# icboard.net
KiCad netlist of a schematic drawn in EAGLE
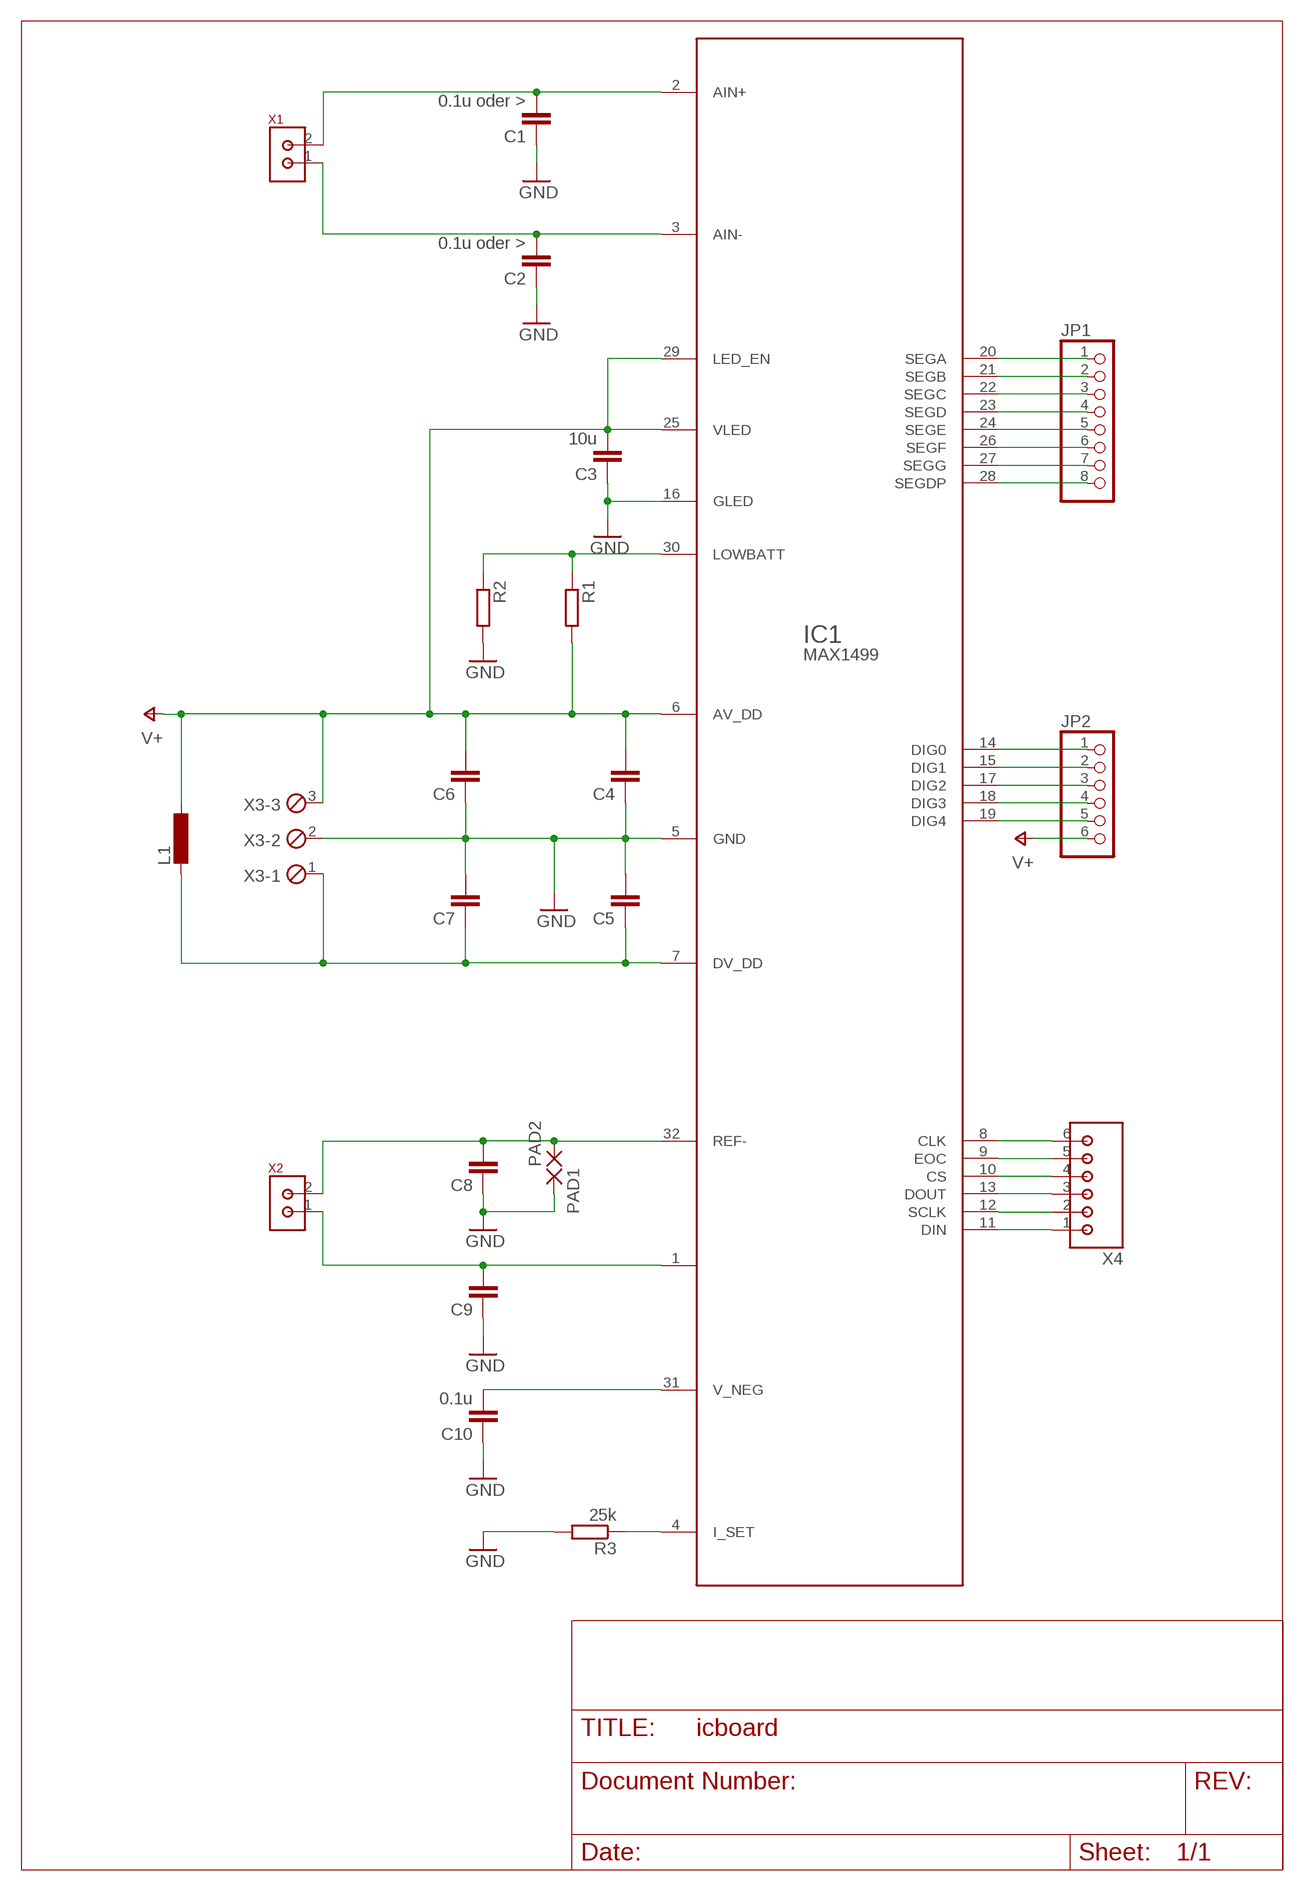
[diagram p0: schematic, sheet 1]

(export (version "E")
  (design (tool "Eeschema 10.0.6"))
  (components
    (comp (ref "C1")
      (value "0.1u oder >")
      (footprint "eagle-import:C0603")
      (libsource (lib "eagle-import") (part "C-EUC0603"))
    )
    (comp (ref "C2")
      (value "0.1u oder >")
      (footprint "eagle-import:C0603")
      (libsource (lib "eagle-import") (part "C-EUC0603"))
    )
    (comp (ref "C3")
      (value "10u")
      (footprint "eagle-import:C0603")
      (libsource (lib "eagle-import") (part "C-EUC0603"))
    )
    (comp (ref "C4")
      (value "C-EUC0603")
      (footprint "eagle-import:C0603")
      (libsource (lib "eagle-import") (part "C-EUC0603"))
    )
    (comp (ref "C5")
      (value "C-EUC0603")
      (footprint "eagle-import:C0603")
      (libsource (lib "eagle-import") (part "C-EUC0603"))
    )
    (comp (ref "C6")
      (value "C-EUC0603")
      (footprint "eagle-import:C0603")
      (libsource (lib "eagle-import") (part "C-EUC0603"))
    )
    (comp (ref "C7")
      (value "C-EUC0603")
      (footprint "eagle-import:C0603")
      (libsource (lib "eagle-import") (part "C-EUC0603"))
    )
    (comp (ref "C8")
      (value "C-EUC0603")
      (footprint "eagle-import:C0603")
      (libsource (lib "eagle-import") (part "C-EUC0603"))
    )
    (comp (ref "C9")
      (value "C-EUC0603")
      (footprint "eagle-import:C0603")
      (libsource (lib "eagle-import") (part "C-EUC0603"))
    )
    (comp (ref "C10")
      (value "0.1u")
      (footprint "eagle-import:C0603")
      (libsource (lib "eagle-import") (part "C-EUC0603"))
    )
    (comp (ref "IC1")
      (value "MAX1499")
      (footprint "eagle-import:TQFP32-08")
      (libsource (lib "eagle-import") (part "MAX1499"))
    )
    (comp (ref "JP1")
      (value "PINHD-1X8")
      (footprint "eagle-import:1X08")
      (libsource (lib "eagle-import") (part "PINHD-1X8"))
    )
    (comp (ref "JP2")
      (value "PINHD-1X6")
      (footprint "eagle-import:1X06")
      (libsource (lib "eagle-import") (part "PINHD-1X6"))
    )
    (comp (ref "L1")
      (value "L-EUL1812")
      (footprint "eagle-import:L1812")
      (libsource (lib "eagle-import") (part "L-EUL1812"))
    )
    (comp (ref "PAD1")
      (value "SMD2")
      (footprint "eagle-import:SMD1,27-2,54")
      (libsource (lib "eagle-import") (part "SMD2"))
    )
    (comp (ref "PAD2")
      (value "SMD2")
      (footprint "eagle-import:SMD1,27-2,54")
      (libsource (lib "eagle-import") (part "SMD2"))
    )
    (comp (ref "R1")
      (value "R-EU_R0603")
      (footprint "eagle-import:R0603")
      (libsource (lib "eagle-import") (part "R-EU_R0603"))
    )
    (comp (ref "R2")
      (value "R-EU_R0603")
      (footprint "eagle-import:R0603")
      (libsource (lib "eagle-import") (part "R-EU_R0603"))
    )
    (comp (ref "R3")
      (value "25k")
      (footprint "eagle-import:R0603")
      (libsource (lib "eagle-import") (part "R-EU_R0603"))
    )
    (comp (ref "X1")
      (value "MOLEX_CON2_2P")
      (footprint "eagle-import:CON2_2P")
      (libsource (lib "eagle-import") (part "MOLEX_CON2_2P"))
    )
    (comp (ref "X2")
      (value "MOLEX_CON2_2P")
      (footprint "eagle-import:CON2_2P")
      (libsource (lib "eagle-import") (part "MOLEX_CON2_2P"))
    )
    (comp (ref "X3")
      (value "MPT3")
      (footprint "eagle-import:3POL254")
      (libsource (lib "eagle-import") (part "MPT3"))
    )
    (comp (ref "X4")
      (value "MOLEX_CON2_6P")
      (footprint "eagle-import:CON2_6P")
      (libsource (lib "eagle-import") (part "MOLEX_CON2_6P"))
    )
  )
  (nets
    (net (code "1") (name "GND") (class "Default")
      (node (ref "C1") (pin "1") (pinfunction "1_1") (pintype "passive"))
      (node (ref "C10") (pin "1") (pinfunction "1_1") (pintype "passive"))
      (node (ref "C2") (pin "1") (pinfunction "1_1") (pintype "passive"))
      (node (ref "C3") (pin "1") (pinfunction "1_1") (pintype "passive"))
      (node (ref "C4") (pin "1") (pinfunction "1_1") (pintype "passive"))
      (node (ref "C5") (pin "2") (pinfunction "2_2") (pintype "passive"))
      (node (ref "C6") (pin "1") (pinfunction "1_1") (pintype "passive"))
      (node (ref "C7") (pin "2") (pinfunction "2_2") (pintype "passive"))
      (node (ref "C8") (pin "1") (pinfunction "1_1") (pintype "passive"))
      (node (ref "C9") (pin "1") (pinfunction "1_1") (pintype "passive"))
      (node (ref "IC1") (pin "16") (pinfunction "GLED_16") (pintype "input"))
      (node (ref "IC1") (pin "5") (pinfunction "GND_5") (pintype "passive"))
      (node (ref "PAD1") (pin "1") (pinfunction "P_1") (pintype "passive"))
      (node (ref "R2") (pin "2") (pinfunction "2_2") (pintype "passive"))
      (node (ref "R3") (pin "2") (pinfunction "2_2") (pintype "passive"))
      (node (ref "X3") (pin "2") (pinfunction "1_2") (pintype "passive"))
    )
    (net (code "2") (name "Net-(IC1-AIN+)") (class "Default")
      (node (ref "C1") (pin "2") (pinfunction "2_2") (pintype "passive"))
      (node (ref "IC1") (pin "2") (pinfunction "AIN+_2") (pintype "input"))
      (node (ref "X1") (pin "2") (pinfunction "P$2_2") (pintype "bidirectional"))
    )
    (net (code "3") (name "Net-(IC1-AIN-)") (class "Default")
      (node (ref "C2") (pin "2") (pinfunction "2_2") (pintype "passive"))
      (node (ref "IC1") (pin "3") (pinfunction "AIN-_3") (pintype "input"))
      (node (ref "X1") (pin "1") (pinfunction "P$1_1") (pintype "bidirectional"))
    )
    (net (code "4") (name "Net-(IC1-CLK)") (class "Default")
      (node (ref "IC1") (pin "8") (pinfunction "CLK_8") (pintype "input"))
      (node (ref "X4") (pin "6") (pinfunction "6_6") (pintype "bidirectional"))
    )
    (net (code "5") (name "Net-(IC1-CS)") (class "Default")
      (node (ref "IC1") (pin "10") (pinfunction "CS_10") (pintype "input"))
      (node (ref "X4") (pin "4") (pinfunction "4_4") (pintype "bidirectional"))
    )
    (net (code "6") (name "Net-(IC1-DIG0)") (class "Default")
      (node (ref "IC1") (pin "14") (pinfunction "DIG0_14") (pintype "input"))
      (node (ref "JP2") (pin "1") (pinfunction "1_1") (pintype "passive"))
    )
    (net (code "7") (name "Net-(IC1-DIG1)") (class "Default")
      (node (ref "IC1") (pin "15") (pinfunction "DIG1_15") (pintype "input"))
      (node (ref "JP2") (pin "2") (pinfunction "2_2") (pintype "passive"))
    )
    (net (code "8") (name "Net-(IC1-DIG2)") (class "Default")
      (node (ref "IC1") (pin "17") (pinfunction "DIG2_17") (pintype "input"))
      (node (ref "JP2") (pin "3") (pinfunction "3_3") (pintype "passive"))
    )
    (net (code "9") (name "Net-(IC1-DIG3)") (class "Default")
      (node (ref "IC1") (pin "18") (pinfunction "DIG3_18") (pintype "input"))
      (node (ref "JP2") (pin "4") (pinfunction "4_4") (pintype "passive"))
    )
    (net (code "10") (name "Net-(IC1-DIG4)") (class "Default")
      (node (ref "IC1") (pin "19") (pinfunction "DIG4_19") (pintype "input"))
      (node (ref "JP2") (pin "5") (pinfunction "5_5") (pintype "passive"))
    )
    (net (code "11") (name "Net-(IC1-DIN)") (class "Default")
      (node (ref "IC1") (pin "11") (pinfunction "DIN_11") (pintype "input"))
      (node (ref "X4") (pin "1") (pinfunction "1_1") (pintype "bidirectional"))
    )
    (net (code "12") (name "Net-(IC1-DOUT)") (class "Default")
      (node (ref "IC1") (pin "13") (pinfunction "DOUT_13") (pintype "output"))
      (node (ref "X4") (pin "3") (pinfunction "3_3") (pintype "bidirectional"))
    )
    (net (code "13") (name "Net-(IC1-DV_DD)") (class "Default")
      (node (ref "C5") (pin "1") (pinfunction "1_1") (pintype "passive"))
      (node (ref "C7") (pin "1") (pinfunction "1_1") (pintype "passive"))
      (node (ref "IC1") (pin "7") (pinfunction "DV_DD_7") (pintype "passive"))
      (node (ref "L1") (pin "2") (pinfunction "2_2") (pintype "passive"))
      (node (ref "X3") (pin "1") (pinfunction "1_1") (pintype "passive"))
    )
    (net (code "14") (name "Net-(IC1-EOC)") (class "Default")
      (node (ref "IC1") (pin "9") (pinfunction "EOC_9") (pintype "output"))
      (node (ref "X4") (pin "5") (pinfunction "5_5") (pintype "bidirectional"))
    )
    (net (code "15") (name "Net-(IC1-I_SET)") (class "Default")
      (node (ref "IC1") (pin "4") (pinfunction "I_SET_4") (pintype "input"))
      (node (ref "R3") (pin "1") (pinfunction "1_1") (pintype "passive"))
    )
    (net (code "16") (name "Net-(IC1-LOWBATT)") (class "Default")
      (node (ref "IC1") (pin "30") (pinfunction "LOWBATT_30") (pintype "passive"))
      (node (ref "R1") (pin "1") (pinfunction "1_1") (pintype "passive"))
      (node (ref "R2") (pin "1") (pinfunction "1_1") (pintype "passive"))
    )
    (net (code "17") (name "Net-(IC1-REF+)") (class "Default")
      (node (ref "C9") (pin "2") (pinfunction "2_2") (pintype "passive"))
      (node (ref "IC1") (pin "1") (pinfunction "REF+_1") (pintype "input"))
      (node (ref "X2") (pin "1") (pinfunction "P$1_1") (pintype "bidirectional"))
    )
    (net (code "18") (name "Net-(IC1-REF-)") (class "Default")
      (node (ref "C8") (pin "2") (pinfunction "2_2") (pintype "passive"))
      (node (ref "IC1") (pin "32") (pinfunction "REF-_32") (pintype "input"))
      (node (ref "PAD2") (pin "1") (pinfunction "P_1") (pintype "passive"))
      (node (ref "X2") (pin "2") (pinfunction "P$2_2") (pintype "bidirectional"))
    )
    (net (code "19") (name "Net-(IC1-SCLK)") (class "Default")
      (node (ref "IC1") (pin "12") (pinfunction "SCLK_12") (pintype "input"))
      (node (ref "X4") (pin "2") (pinfunction "2_2") (pintype "bidirectional"))
    )
    (net (code "20") (name "Net-(IC1-SEGA)") (class "Default")
      (node (ref "IC1") (pin "20") (pinfunction "SEGA_20") (pintype "output"))
      (node (ref "JP1") (pin "1") (pinfunction "1_1") (pintype "passive"))
    )
    (net (code "21") (name "Net-(IC1-SEGB)") (class "Default")
      (node (ref "IC1") (pin "21") (pinfunction "SEGB_21") (pintype "output"))
      (node (ref "JP1") (pin "2") (pinfunction "2_2") (pintype "passive"))
    )
    (net (code "22") (name "Net-(IC1-SEGC)") (class "Default")
      (node (ref "IC1") (pin "22") (pinfunction "SEGC_22") (pintype "output"))
      (node (ref "JP1") (pin "3") (pinfunction "3_3") (pintype "passive"))
    )
    (net (code "23") (name "Net-(IC1-SEGD)") (class "Default")
      (node (ref "IC1") (pin "23") (pinfunction "SEGD_23") (pintype "output"))
      (node (ref "JP1") (pin "4") (pinfunction "4_4") (pintype "passive"))
    )
    (net (code "24") (name "Net-(IC1-SEGDP)") (class "Default")
      (node (ref "IC1") (pin "28") (pinfunction "SEGDP_28") (pintype "output"))
      (node (ref "JP1") (pin "8") (pinfunction "8_8") (pintype "passive"))
    )
    (net (code "25") (name "Net-(IC1-SEGE)") (class "Default")
      (node (ref "IC1") (pin "24") (pinfunction "SEGE_24") (pintype "output"))
      (node (ref "JP1") (pin "5") (pinfunction "5_5") (pintype "passive"))
    )
    (net (code "26") (name "Net-(IC1-SEGF)") (class "Default")
      (node (ref "IC1") (pin "26") (pinfunction "SEGF_26") (pintype "output"))
      (node (ref "JP1") (pin "6") (pinfunction "6_6") (pintype "passive"))
    )
    (net (code "27") (name "Net-(IC1-SEGG)") (class "Default")
      (node (ref "IC1") (pin "27") (pinfunction "SEGG_27") (pintype "output"))
      (node (ref "JP1") (pin "7") (pinfunction "7_7") (pintype "passive"))
    )
    (net (code "28") (name "Net-(IC1-V_NEG)") (class "Default")
      (node (ref "C10") (pin "2") (pinfunction "2_2") (pintype "passive"))
      (node (ref "IC1") (pin "31") (pinfunction "V_NEG_31") (pintype "passive"))
    )
    (net (code "29") (name "V+") (class "Default")
      (node (ref "C3") (pin "2") (pinfunction "2_2") (pintype "passive"))
      (node (ref "C4") (pin "2") (pinfunction "2_2") (pintype "passive"))
      (node (ref "C6") (pin "2") (pinfunction "2_2") (pintype "passive"))
      (node (ref "IC1") (pin "25") (pinfunction "VLED_25") (pintype "input"))
      (node (ref "IC1") (pin "29") (pinfunction "LED_EN_29") (pintype "input"))
      (node (ref "IC1") (pin "6") (pinfunction "AV_DD_6") (pintype "passive"))
      (node (ref "JP2") (pin "6") (pinfunction "6_6") (pintype "passive"))
      (node (ref "L1") (pin "1") (pinfunction "1_1") (pintype "passive"))
      (node (ref "R1") (pin "2") (pinfunction "2_2") (pintype "passive"))
      (node (ref "X3") (pin "3") (pinfunction "1_3") (pintype "passive"))
    )
  )
)
